# WIFI.net
KiCad netlist of a schematic drawn in Altium Designer
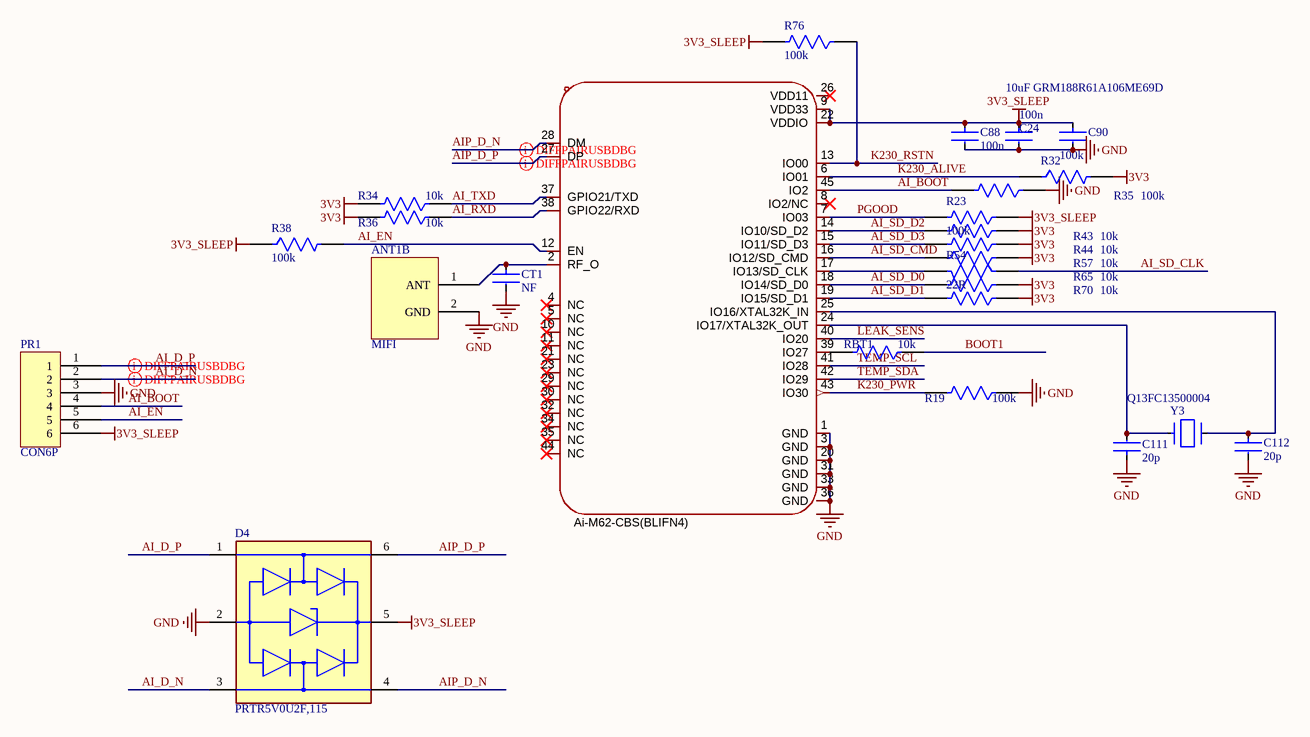
[diagram p0: WIFI.SchDoc]

(export (version "E")
  (design (tool "Eeschema 10.0.6"))
  (components
    (comp (ref "ANT1") (value "MIFI") (footprint "IFA_MAGUS") (libsource (lib "LEAKCAM") (part "MIFI")))
    (comp (ref "C24")
      (value "100n")
      (footprint "CAP_0402")
      (description "C307331")
      (fields (field (name "TOLERANCE") "10%"))
      (libsource (lib "LEAKCAM") (part "CMP-03422-001116-1"))
    )
    (comp (ref "C88")
      (value "100n")
      (footprint "CAP_0402")
      (description "C307331")
      (fields (field (name "TOLERANCE") "10%"))
      (libsource (lib "LEAKCAM") (part "CMP-03422-001116-1"))
    )
    (comp (ref "C90")
      (value "10uF GRM188R61A106ME69D")
      (footprint "FP-GRM188-0_15-MFG")
      (description "C19702")
      (fields (field (name "TOLERANCE") "20%"))
      (libsource (lib "LEAKCAM") (part "CMP-06035-003612-1"))
    )
    (comp (ref "C111")
      (value "20p")
      (footprint "CAP_0402")
      (description "C1554")
      (fields (field (name "TOLERANCE") "10%"))
      (libsource (lib "LEAKCAM") (part "CMP-03422-001116-1"))
    )
    (comp (ref "C112")
      (value "20p")
      (footprint "CAP_0402")
      (description "C1554")
      (fields (field (name "TOLERANCE") "10%"))
      (libsource (lib "LEAKCAM") (part "CMP-03422-001116-1"))
    )
    (comp (ref "CT1")
      (value "NF")
      (footprint "CAP_0402")
      (fields (field (name "TOLERANCE") "10%"))
      (libsource (lib "LEAKCAM") (part "CMP-03422-001116-1"))
    )
    (comp (ref "D4")
      (value "PRTR5V0U2F,115")
      (footprint "FP-SOT886-MFG")
      (description "C478118")
      (fields
        (field (name "OCTOPART") "https://octopart.com/prtr5v0u2f%2C115-nexperia-78741690")
        (field (name "MANUFACTURER") "Nexperia")
      )
      (libsource (lib "LEAKCAM") (part "CMP-14436-000003-1"))
    )
    (comp (ref "PR1") (value "CON6P") (footprint "CON6P") (libsource (lib "LEAKCAM") (part "CON6P")))
    (comp (ref "R19")
      (value "100k")
      (footprint "RES_0402")
      (description "C25741")
      (fields (field (name "TOLERANCE") "1%"))
      (libsource (lib "LEAKCAM") (part "CMP-03412-016018-1"))
    )
    (comp (ref "R23")
      (value "100k")
      (footprint "RES_0402")
      (description "C25741")
      (fields (field (name "TOLERANCE") "1%"))
      (libsource (lib "LEAKCAM") (part "CMP-03412-016018-1"))
    )
    (comp (ref "R32")
      (value "100k")
      (footprint "RES_0402")
      (description "C25741")
      (fields (field (name "TOLERANCE") "1%"))
      (libsource (lib "LEAKCAM") (part "CMP-03412-016018-1"))
    )
    (comp (ref "R34")
      (value "10k")
      (footprint "RES_0402")
      (description "C25744")
      (fields (field (name "TOLERANCE") "1%"))
      (libsource (lib "LEAKCAM") (part "CMP-03412-016018-1"))
    )
    (comp (ref "R35")
      (value "100k")
      (footprint "RES_0402")
      (description "C25741")
      (fields (field (name "TOLERANCE") "1%"))
      (libsource (lib "LEAKCAM") (part "CMP-03412-016018-1"))
    )
    (comp (ref "R36")
      (value "10k")
      (footprint "RES_0402")
      (description "C25744")
      (fields (field (name "TOLERANCE") "1%"))
      (libsource (lib "LEAKCAM") (part "CMP-03412-016018-1"))
    )
    (comp (ref "R38")
      (value "100k")
      (footprint "RES_0402")
      (description "C25741")
      (fields (field (name "TOLERANCE") "1%"))
      (libsource (lib "LEAKCAM") (part "CMP-03412-016018-1"))
    )
    (comp (ref "R43")
      (value "10k")
      (footprint "RES_0402")
      (description "C25744")
      (fields (field (name "TOLERANCE") "1%"))
      (libsource (lib "LEAKCAM") (part "CMP-03412-016018-1"))
    )
    (comp (ref "R44")
      (value "10k")
      (footprint "RES_0402")
      (description "C25744")
      (fields (field (name "TOLERANCE") "1%"))
      (libsource (lib "LEAKCAM") (part "CMP-03412-016018-1"))
    )
    (comp (ref "R54")
      (value "22R")
      (footprint "RES_0402")
      (description "C25092")
      (fields (field (name "TOLERANCE") "1%"))
      (libsource (lib "LEAKCAM") (part "CMP-03412-016018-1"))
    )
    (comp (ref "R57")
      (value "10k")
      (footprint "RES_0402")
      (description "C25744")
      (fields (field (name "TOLERANCE") "1%"))
      (libsource (lib "LEAKCAM") (part "CMP-03412-016018-1"))
    )
    (comp (ref "R65")
      (value "10k")
      (footprint "RES_0402")
      (description "C25744")
      (fields (field (name "TOLERANCE") "1%"))
      (libsource (lib "LEAKCAM") (part "CMP-03412-016018-1"))
    )
    (comp (ref "R70")
      (value "10k")
      (footprint "RES_0402")
      (description "C25744")
      (fields (field (name "TOLERANCE") "1%"))
      (libsource (lib "LEAKCAM") (part "CMP-03412-016018-1"))
    )
    (comp (ref "R76")
      (value "100k")
      (footprint "RES_0402")
      (description "C25741")
      (fields (field (name "TOLERANCE") "1%"))
      (libsource (lib "LEAKCAM") (part "CMP-03412-016018-1"))
    )
    (comp (ref "RBT1")
      (value "10k")
      (footprint "RES_0402")
      (description "C25744")
      (fields (field (name "TOLERANCE") "1%"))
      (libsource (lib "LEAKCAM") (part "CMP-03412-016018-1"))
    )
    (comp (ref "U11")
      (value "ai-m62-cbs(blifn4)")
      (footprint "AI-M62-CBS")
      (description "C41368035")
      (fields
        (field (name "MANUFACTURER") "Ai-Thinker(安信可)")
        (field (name "MANUFACTURERPART") "Ai-M62-CBS(BLIFN4)")
        (field (name "UTILIZED IC / PART") "BL616")
      )
      (libsource (lib "LEAKCAM") (part "ai-m62-cbs(blifn4)"))
    )
    (comp (ref "Y3")
      (value "Q13FC13500004")
      (footprint "FP-ABS07-MFG")
      (description "C32346")
      (fields (field (name "TOLERANCE") "20ppm"))
      (libsource (lib "LEAKCAM") (part "CMP-0447-00001-4"))
    )
  )
  (nets
    (net (code "1") (name "/AIP_D_N") (class "Default")
      (node (ref "D4") (pin "4") (pinfunction "I/O2_4") (pintype "passive"))
      (node (ref "U11") (pin "28") (pinfunction "DM_28") (pintype "passive"))
    )
    (net (code "2") (name "/AIP_D_P") (class "Default")
      (node (ref "D4") (pin "6") (pinfunction "I/O1_6") (pintype "passive"))
      (node (ref "U11") (pin "27") (pinfunction "DP_27") (pintype "passive"))
    )
    (net (code "3") (name "/AI_BOOT") (class "Default")
      (node (ref "PR1") (pin "4") (pinfunction "4_4") (pintype "passive"))
      (node (ref "R35") (pin "2") (pinfunction "2_2") (pintype "passive"))
      (node (ref "U11") (pin "45") (pinfunction "IO2_45") (pintype "passive"))
    )
    (net (code "4") (name "/AI_D_N") (class "Default")
      (node (ref "D4") (pin "3") (pinfunction "I/O2_3") (pintype "passive"))
      (node (ref "PR1") (pin "2") (pinfunction "2_2") (pintype "passive"))
    )
    (net (code "5") (name "/AI_D_P") (class "Default")
      (node (ref "D4") (pin "1") (pinfunction "I/O1_1") (pintype "passive"))
      (node (ref "PR1") (pin "1") (pinfunction "1_1") (pintype "passive"))
    )
    (net (code "6") (name "/AI_EN") (class "Default")
      (node (ref "PR1") (pin "5") (pinfunction "5_5") (pintype "passive"))
      (node (ref "R38") (pin "2") (pinfunction "2_2") (pintype "passive"))
      (node (ref "U11") (pin "12") (pinfunction "EN_12") (pintype "passive"))
    )
    (net (code "7") (name "/AI_RXD") (class "Default")
      (node (ref "R36") (pin "1") (pinfunction "1_1") (pintype "passive"))
      (node (ref "U11") (pin "38") (pinfunction "GPIO22/RXD_38") (pintype "passive"))
    )
    (net (code "8") (name "/AI_SD_CLK") (class "Default")
      (node (ref "R54") (pin "1") (pinfunction "1_1") (pintype "passive"))
    )
    (net (code "9") (name "/AI_SD_CMD") (class "Default")
      (node (ref "R57") (pin "2") (pinfunction "2_2") (pintype "passive"))
      (node (ref "U11") (pin "16") (pinfunction "IO12/SD_CMD_16") (pintype "passive"))
    )
    (net (code "10") (name "/AI_SD_D0") (class "Default")
      (node (ref "R65") (pin "2") (pinfunction "2_2") (pintype "passive"))
      (node (ref "U11") (pin "18") (pinfunction "IO14/SD_D0_18") (pintype "passive"))
    )
    (net (code "11") (name "/AI_SD_D1") (class "Default")
      (node (ref "R70") (pin "2") (pinfunction "2_2") (pintype "passive"))
      (node (ref "U11") (pin "19") (pinfunction "IO15/SD_D1_19") (pintype "passive"))
    )
    (net (code "12") (name "/AI_SD_D2") (class "Default")
      (node (ref "R43") (pin "2") (pinfunction "2_2") (pintype "passive"))
      (node (ref "U11") (pin "14") (pinfunction "IO10/SD_D2_14") (pintype "passive"))
    )
    (net (code "13") (name "/AI_SD_D3") (class "Default")
      (node (ref "R44") (pin "2") (pinfunction "2_2") (pintype "passive"))
      (node (ref "U11") (pin "15") (pinfunction "IO11/SD_D3_15") (pintype "passive"))
    )
    (net (code "14") (name "/AI_TXD") (class "Default")
      (node (ref "R34") (pin "1") (pinfunction "1_1") (pintype "passive"))
      (node (ref "U11") (pin "37") (pinfunction "GPIO21/TXD_37") (pintype "passive"))
    )
    (net (code "15") (name "/BOOT1") (class "Default")
      (node (ref "RBT1") (pin "1") (pinfunction "1_1") (pintype "passive"))
    )
    (net (code "16") (name "/K230_ALIVE") (class "Default")
      (node (ref "R32") (pin "1") (pinfunction "1_1") (pintype "passive"))
      (node (ref "U11") (pin "6") (pinfunction "IO01_6") (pintype "passive"))
    )
    (net (code "17") (name "/K230_PWR") (class "Default")
      (node (ref "R19") (pin "2") (pinfunction "2_2") (pintype "passive"))
      (node (ref "U11") (pin "43") (pinfunction "IO30_43") (pintype "output"))
    )
    (net (code "18") (name "/K230_RSTN") (class "Default")
      (node (ref "R76") (pin "1") (pinfunction "1_1") (pintype "passive"))
      (node (ref "U11") (pin "13") (pinfunction "IO00_13") (pintype "passive"))
    )
    (net (code "19") (name "/LEAK_SENS") (class "Default")
      (node (ref "U11") (pin "40") (pinfunction "IO20_40") (pintype "passive"))
    )
    (net (code "20") (name "/PGOOD") (class "Default")
      (node (ref "R23") (pin "2") (pinfunction "2_2") (pintype "passive"))
      (node (ref "U11") (pin "7") (pinfunction "IO03_7") (pintype "passive"))
    )
    (net (code "21") (name "/TEMP_SCL") (class "Default")
      (node (ref "U11") (pin "41") (pinfunction "IO28_41") (pintype "passive"))
    )
    (net (code "22") (name "/TEMP_SDA") (class "Default")
      (node (ref "U11") (pin "42") (pinfunction "IO29_42") (pintype "passive"))
    )
    (net (code "23") (name "3V3") (class "Default")
      (node (ref "R32") (pin "2") (pinfunction "2_2") (pintype "passive"))
      (node (ref "R34") (pin "2") (pinfunction "2_2") (pintype "passive"))
      (node (ref "R36") (pin "2") (pinfunction "2_2") (pintype "passive"))
      (node (ref "R43") (pin "1") (pinfunction "1_1") (pintype "passive"))
      (node (ref "R44") (pin "1") (pinfunction "1_1") (pintype "passive"))
      (node (ref "R57") (pin "1") (pinfunction "1_1") (pintype "passive"))
      (node (ref "R65") (pin "1") (pinfunction "1_1") (pintype "passive"))
      (node (ref "R70") (pin "1") (pinfunction "1_1") (pintype "passive"))
    )
    (net (code "24") (name "3V3_SLEEP") (class "Default")
      (node (ref "C24") (pin "1") (pinfunction "1_1") (pintype "passive"))
      (node (ref "C88") (pin "1") (pinfunction "1_1") (pintype "passive"))
      (node (ref "C90") (pin "1") (pinfunction "1_1") (pintype "passive"))
      (node (ref "D4") (pin "5") (pinfunction "VCC_5") (pintype "power_in"))
      (node (ref "PR1") (pin "6") (pinfunction "6_6") (pintype "passive"))
      (node (ref "R23") (pin "1") (pinfunction "1_1") (pintype "passive"))
      (node (ref "R38") (pin "1") (pinfunction "1_1") (pintype "passive"))
      (node (ref "R76") (pin "2") (pinfunction "2_2") (pintype "passive"))
      (node (ref "U11") (pin "22") (pinfunction "VDDIO_22") (pintype "passive"))
      (node (ref "U11") (pin "9") (pinfunction "VDD33_9") (pintype "passive"))
    )
    (net (code "25") (name "GND") (class "Default")
      (node (ref "ANT1") (pin "2") (pinfunction "GND_2") (pintype "passive"))
      (node (ref "C111") (pin "1") (pinfunction "1_1") (pintype "passive"))
      (node (ref "C112") (pin "2") (pinfunction "2_2") (pintype "passive"))
      (node (ref "C24") (pin "2") (pinfunction "2_2") (pintype "passive"))
      (node (ref "C88") (pin "2") (pinfunction "2_2") (pintype "passive"))
      (node (ref "C90") (pin "2") (pinfunction "2_2") (pintype "passive"))
      (node (ref "CT1") (pin "2") (pinfunction "2_2") (pintype "passive"))
      (node (ref "D4") (pin "2") (pinfunction "GND_2") (pintype "power_in"))
      (node (ref "PR1") (pin "3") (pinfunction "3_3") (pintype "passive"))
      (node (ref "R19") (pin "1") (pinfunction "1_1") (pintype "passive"))
      (node (ref "R35") (pin "1") (pinfunction "1_1") (pintype "passive"))
      (node (ref "U11") (pin "1") (pinfunction "GND_1") (pintype "passive"))
      (node (ref "U11") (pin "20") (pinfunction "GND_20") (pintype "passive"))
      (node (ref "U11") (pin "3") (pinfunction "GND_3") (pintype "passive"))
      (node (ref "U11") (pin "31") (pinfunction "GND_31") (pintype "passive"))
      (node (ref "U11") (pin "33") (pinfunction "GND_33") (pintype "passive"))
      (node (ref "U11") (pin "36") (pinfunction "GND_36") (pintype "passive"))
    )
    (net (code "26") (name "Net-(ANT1B-ANT)") (class "Default")
      (node (ref "ANT1") (pin "1") (pinfunction "ANT_1") (pintype "passive"))
      (node (ref "CT1") (pin "1") (pinfunction "1_1") (pintype "passive"))
      (node (ref "U11") (pin "2") (pinfunction "RF_O_2") (pintype "passive"))
    )
    (net (code "27") (name "Net-(U11-IO13{slash}SD_CLK)") (class "Default")
      (node (ref "R54") (pin "2") (pinfunction "2_2") (pintype "passive"))
      (node (ref "U11") (pin "17") (pinfunction "IO13/SD_CLK_17") (pintype "passive"))
    )
    (net (code "28") (name "Net-(U11-IO16{slash}XTAL32K_IN)") (class "Default")
      (node (ref "C112") (pin "1") (pinfunction "1_1") (pintype "passive"))
      (node (ref "U11") (pin "25") (pinfunction "IO16/XTAL32K_IN_25") (pintype "passive"))
      (node (ref "Y3") (pin "2") (pinfunction "2_2") (pintype "passive"))
    )
    (net (code "29") (name "Net-(U11-IO17{slash}XTAL32K_OUT)") (class "Default")
      (node (ref "C111") (pin "2") (pinfunction "2_2") (pintype "passive"))
      (node (ref "U11") (pin "24") (pinfunction "IO17/XTAL32K_OUT_24") (pintype "passive"))
      (node (ref "Y3") (pin "1") (pinfunction "1_1") (pintype "passive"))
    )
    (net (code "30") (name "Net-(U11-IO27)") (class "Default")
      (node (ref "RBT1") (pin "2") (pinfunction "2_2") (pintype "passive"))
      (node (ref "U11") (pin "39") (pinfunction "IO27_39") (pintype "passive"))
    )
    (net (code "31") (name "unconnected-(U11-IO2{slash}NC-Pad8)") (class "Default")
      (node (ref "U11") (pin "8") (pinfunction "IO2/NC_8") (pintype "passive+no_connect"))
    )
    (net (code "32") (name "unconnected-(U11-NC-Pad4)") (class "Default")
      (node (ref "U11") (pin "4") (pinfunction "NC_4") (pintype "passive+no_connect"))
    )
    (net (code "33") (name "unconnected-(U11-NC-Pad5)") (class "Default")
      (node (ref "U11") (pin "5") (pinfunction "NC_5") (pintype "passive+no_connect"))
    )
    (net (code "34") (name "unconnected-(U11-NC-Pad10)") (class "Default")
      (node (ref "U11") (pin "10") (pinfunction "NC_10") (pintype "passive+no_connect"))
    )
    (net (code "35") (name "unconnected-(U11-NC-Pad11)") (class "Default")
      (node (ref "U11") (pin "11") (pinfunction "NC_11") (pintype "passive+no_connect"))
    )
    (net (code "36") (name "unconnected-(U11-NC-Pad21)") (class "Default")
      (node (ref "U11") (pin "21") (pinfunction "NC_21") (pintype "passive+no_connect"))
    )
    (net (code "37") (name "unconnected-(U11-NC-Pad23)") (class "Default")
      (node (ref "U11") (pin "23") (pinfunction "NC_23") (pintype "passive+no_connect"))
    )
    (net (code "38") (name "unconnected-(U11-NC-Pad29)") (class "Default")
      (node (ref "U11") (pin "29") (pinfunction "NC_29") (pintype "passive+no_connect"))
    )
    (net (code "39") (name "unconnected-(U11-NC-Pad30)") (class "Default")
      (node (ref "U11") (pin "30") (pinfunction "NC_30") (pintype "passive+no_connect"))
    )
    (net (code "40") (name "unconnected-(U11-NC-Pad32)") (class "Default")
      (node (ref "U11") (pin "32") (pinfunction "NC_32") (pintype "passive+no_connect"))
    )
    (net (code "41") (name "unconnected-(U11-NC-Pad34)") (class "Default")
      (node (ref "U11") (pin "34") (pinfunction "NC_34") (pintype "passive+no_connect"))
    )
    (net (code "42") (name "unconnected-(U11-NC-Pad35)") (class "Default")
      (node (ref "U11") (pin "35") (pinfunction "NC_35") (pintype "passive+no_connect"))
    )
    (net (code "43") (name "unconnected-(U11-NC-Pad44)") (class "Default")
      (node (ref "U11") (pin "44") (pinfunction "NC_44") (pintype "passive+no_connect"))
    )
    (net (code "44") (name "unconnected-(U11-VDD11-Pad26)") (class "Default")
      (node (ref "U11") (pin "26") (pinfunction "VDD11_26") (pintype "passive+no_connect"))
    )
  )
)
